# USB_Clone.net
KiCad netlist of a schematic drawn in Altium Designer
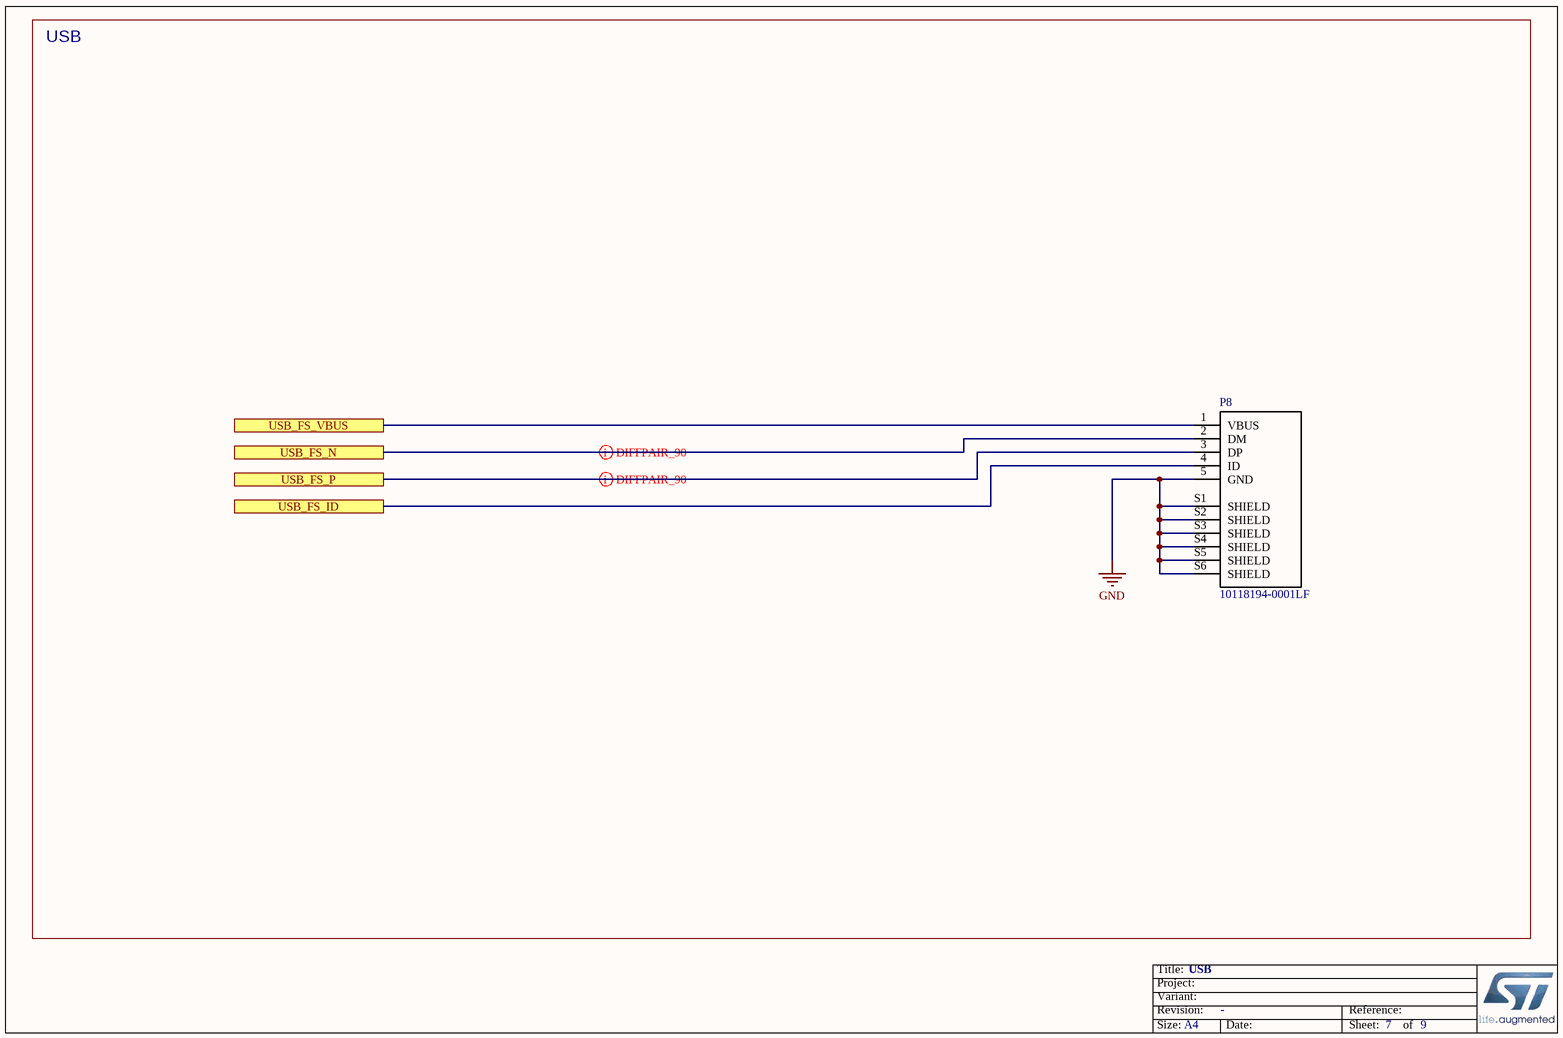
[diagram p0: USB_Clone.SchDoc]

(export (version "E")
  (design (tool "Eeschema 10.0.6"))
  (components
    (comp (ref "P8")
      (value "10118194-0001LF")
      (footprint "USB Micro B Receptacle")
      (description "USB - micro B USB 2.0 Receptacle Connector 5 Position Surface Mount, Right Angle; Through Hole")
      (fields (field (name "MF") "Amphenol ICC (FCI)"))
      (libsource (lib "AltiumLibraries") (part "USB Micro B Receptacle"))
    )
  )
  (nets
    (net (code "1") (name "/USB_FS_ID") (class "Default")
      (node (ref "P8") (pin "4") (pinfunction "ID_4") (pintype "passive"))
    )
    (net (code "2") (name "/USB_FS_N") (class "Default")
      (node (ref "P8") (pin "2") (pinfunction "DM_2") (pintype "passive"))
    )
    (net (code "3") (name "/USB_FS_P") (class "Default")
      (node (ref "P8") (pin "3") (pinfunction "DP_3") (pintype "passive"))
    )
    (net (code "4") (name "/USB_FS_VBUS") (class "Default")
      (node (ref "P8") (pin "1") (pinfunction "VBUS_1") (pintype "passive"))
    )
    (net (code "5") (name "GND") (class "Default")
      (node (ref "P8") (pin "5") (pinfunction "GND_5") (pintype "passive"))
      (node (ref "P8") (pin "S1") (pinfunction "SHIELD_S1") (pintype "passive"))
      (node (ref "P8") (pin "S2") (pinfunction "SHIELD_S2") (pintype "passive"))
      (node (ref "P8") (pin "S3") (pinfunction "SHIELD_S3") (pintype "passive"))
      (node (ref "P8") (pin "S4") (pinfunction "SHIELD_S4") (pintype "passive"))
      (node (ref "P8") (pin "S5") (pinfunction "SHIELD_S5") (pintype "passive"))
      (node (ref "P8") (pin "S6") (pinfunction "SHIELD_S6") (pintype "passive"))
    )
  )
)
